# growleds.net
KiCad netlist of a schematic drawn in EAGLE
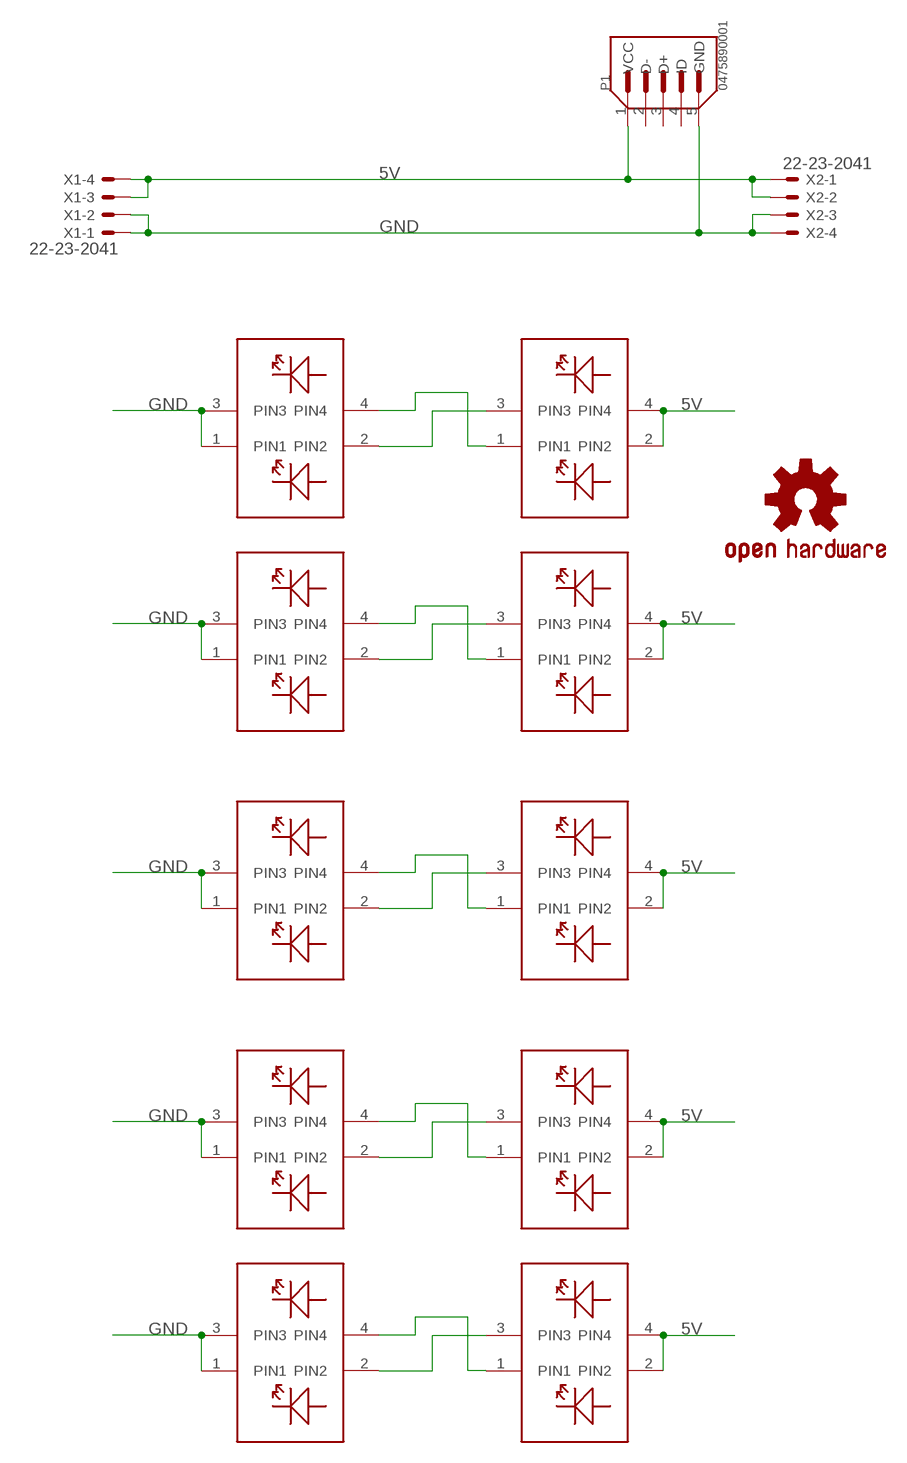
[diagram p0: schematic, sheet 1]

(export (version "E")
  (design (tool "Eeschema 10.0.6"))
  (components
    (comp (ref "LOGO1")
      (value "OSHW-LOGOM-COPPER")
      (footprint "eagle-import:OSHW-LOGO-M_COPPER")
      (libsource (lib "eagle-import") (part "OSHW-LOGOM-COPPER"))
    )
    (comp (ref "P1")
      (value "0475890001")
      (footprint "eagle-import:MOLEX_0475890001")
      (fields (field (name "MF") "Molex"))
      (libsource (lib "eagle-import") (part "0475890001"))
    )
    (comp (ref "U$1")
      (value "RBLED")
      (footprint "eagle-import:4-PLCC")
      (libsource (lib "eagle-import") (part "RBLED"))
    )
    (comp (ref "U$2")
      (value "RBLED")
      (footprint "eagle-import:4-PLCC")
      (libsource (lib "eagle-import") (part "RBLED"))
    )
    (comp (ref "U$3")
      (value "RBLED")
      (footprint "eagle-import:4-PLCC")
      (libsource (lib "eagle-import") (part "RBLED"))
    )
    (comp (ref "U$4")
      (value "RBLED")
      (footprint "eagle-import:4-PLCC")
      (libsource (lib "eagle-import") (part "RBLED"))
    )
    (comp (ref "U$5")
      (value "RBLED")
      (footprint "eagle-import:4-PLCC")
      (libsource (lib "eagle-import") (part "RBLED"))
    )
    (comp (ref "U$6")
      (value "RBLED")
      (footprint "eagle-import:4-PLCC")
      (libsource (lib "eagle-import") (part "RBLED"))
    )
    (comp (ref "U$7")
      (value "RBLED")
      (footprint "eagle-import:4-PLCC")
      (libsource (lib "eagle-import") (part "RBLED"))
    )
    (comp (ref "U$8")
      (value "RBLED")
      (footprint "eagle-import:4-PLCC")
      (libsource (lib "eagle-import") (part "RBLED"))
    )
    (comp (ref "U$9")
      (value "RBLED")
      (footprint "eagle-import:4-PLCC")
      (libsource (lib "eagle-import") (part "RBLED"))
    )
    (comp (ref "U$10")
      (value "RBLED")
      (footprint "eagle-import:4-PLCC")
      (libsource (lib "eagle-import") (part "RBLED"))
    )
    (comp (ref "X1")
      (value "22-23-2041")
      (footprint "eagle-import:22-23-2041")
      (fields (field (name "MF") "MOLEX"))
      (libsource (lib "eagle-import") (part "22-23-2041"))
    )
    (comp (ref "X2")
      (value "22-23-2041")
      (footprint "eagle-import:22-23-2041")
      (fields (field (name "MF") "MOLEX"))
      (libsource (lib "eagle-import") (part "22-23-2041"))
    )
  )
  (nets
    (net (code "1") (name "/5V") (class "Default")
      (node (ref "P1") (pin "1") (pinfunction "VCC_1") (pintype "power_in"))
      (node (ref "U$10") (pin "2") (pinfunction "PIN2_2") (pintype "bidirectional"))
      (node (ref "U$10") (pin "4") (pinfunction "PIN4_4") (pintype "bidirectional"))
      (node (ref "U$2") (pin "2") (pinfunction "PIN2_2") (pintype "bidirectional"))
      (node (ref "U$2") (pin "4") (pinfunction "PIN4_4") (pintype "bidirectional"))
      (node (ref "U$4") (pin "2") (pinfunction "PIN2_2") (pintype "bidirectional"))
      (node (ref "U$4") (pin "4") (pinfunction "PIN4_4") (pintype "bidirectional"))
      (node (ref "U$6") (pin "2") (pinfunction "PIN2_2") (pintype "bidirectional"))
      (node (ref "U$6") (pin "4") (pinfunction "PIN4_4") (pintype "bidirectional"))
      (node (ref "U$8") (pin "2") (pinfunction "PIN2_2") (pintype "bidirectional"))
      (node (ref "U$8") (pin "4") (pinfunction "PIN4_4") (pintype "bidirectional"))
      (node (ref "X1") (pin "3") (pinfunction "S_3") (pintype "passive"))
      (node (ref "X1") (pin "4") (pinfunction "S_4") (pintype "passive"))
      (node (ref "X2") (pin "1") (pinfunction "S_1") (pintype "passive"))
      (node (ref "X2") (pin "2") (pinfunction "S_2") (pintype "passive"))
    )
    (net (code "2") (name "/GND") (class "Default")
      (node (ref "P1") (pin "5") (pinfunction "GND_5") (pintype "power_in"))
      (node (ref "U$1") (pin "1") (pinfunction "PIN1_1") (pintype "bidirectional"))
      (node (ref "U$1") (pin "3") (pinfunction "PIN3_3") (pintype "bidirectional"))
      (node (ref "U$3") (pin "1") (pinfunction "PIN1_1") (pintype "bidirectional"))
      (node (ref "U$3") (pin "3") (pinfunction "PIN3_3") (pintype "bidirectional"))
      (node (ref "U$5") (pin "1") (pinfunction "PIN1_1") (pintype "bidirectional"))
      (node (ref "U$5") (pin "3") (pinfunction "PIN3_3") (pintype "bidirectional"))
      (node (ref "U$7") (pin "1") (pinfunction "PIN1_1") (pintype "bidirectional"))
      (node (ref "U$7") (pin "3") (pinfunction "PIN3_3") (pintype "bidirectional"))
      (node (ref "U$9") (pin "1") (pinfunction "PIN1_1") (pintype "bidirectional"))
      (node (ref "U$9") (pin "3") (pinfunction "PIN3_3") (pintype "bidirectional"))
      (node (ref "X1") (pin "1") (pinfunction "S_1") (pintype "passive"))
      (node (ref "X1") (pin "2") (pinfunction "S_2") (pintype "passive"))
      (node (ref "X2") (pin "3") (pinfunction "S_3") (pintype "passive"))
      (node (ref "X2") (pin "4") (pinfunction "S_4") (pintype "passive"))
    )
    (net (code "3") (name "Net-(U$1-PIN2)") (class "Default")
      (node (ref "U$1") (pin "2") (pinfunction "PIN2_2") (pintype "bidirectional"))
      (node (ref "U$2") (pin "3") (pinfunction "PIN3_3") (pintype "bidirectional"))
    )
    (net (code "4") (name "Net-(U$1-PIN4)") (class "Default")
      (node (ref "U$1") (pin "4") (pinfunction "PIN4_4") (pintype "bidirectional"))
      (node (ref "U$2") (pin "1") (pinfunction "PIN1_1") (pintype "bidirectional"))
    )
    (net (code "5") (name "Net-(U$3-PIN2)") (class "Default")
      (node (ref "U$3") (pin "2") (pinfunction "PIN2_2") (pintype "bidirectional"))
      (node (ref "U$4") (pin "3") (pinfunction "PIN3_3") (pintype "bidirectional"))
    )
    (net (code "6") (name "Net-(U$3-PIN4)") (class "Default")
      (node (ref "U$3") (pin "4") (pinfunction "PIN4_4") (pintype "bidirectional"))
      (node (ref "U$4") (pin "1") (pinfunction "PIN1_1") (pintype "bidirectional"))
    )
    (net (code "7") (name "Net-(U$5-PIN2)") (class "Default")
      (node (ref "U$5") (pin "2") (pinfunction "PIN2_2") (pintype "bidirectional"))
      (node (ref "U$6") (pin "3") (pinfunction "PIN3_3") (pintype "bidirectional"))
    )
    (net (code "8") (name "Net-(U$5-PIN4)") (class "Default")
      (node (ref "U$5") (pin "4") (pinfunction "PIN4_4") (pintype "bidirectional"))
      (node (ref "U$6") (pin "1") (pinfunction "PIN1_1") (pintype "bidirectional"))
    )
    (net (code "9") (name "Net-(U$7-PIN2)") (class "Default")
      (node (ref "U$7") (pin "2") (pinfunction "PIN2_2") (pintype "bidirectional"))
      (node (ref "U$8") (pin "3") (pinfunction "PIN3_3") (pintype "bidirectional"))
    )
    (net (code "10") (name "Net-(U$7-PIN4)") (class "Default")
      (node (ref "U$7") (pin "4") (pinfunction "PIN4_4") (pintype "bidirectional"))
      (node (ref "U$8") (pin "1") (pinfunction "PIN1_1") (pintype "bidirectional"))
    )
    (net (code "11") (name "Net-(U$10-PIN1)") (class "Default")
      (node (ref "U$10") (pin "1") (pinfunction "PIN1_1") (pintype "bidirectional"))
      (node (ref "U$9") (pin "4") (pinfunction "PIN4_4") (pintype "bidirectional"))
    )
    (net (code "12") (name "Net-(U$10-PIN3)") (class "Default")
      (node (ref "U$10") (pin "3") (pinfunction "PIN3_3") (pintype "bidirectional"))
      (node (ref "U$9") (pin "2") (pinfunction "PIN2_2") (pintype "bidirectional"))
    )
    (net (code "13") (name "unconnected-(P1-D+-Pad3)") (class "Default")
      (node (ref "P1") (pin "3") (pinfunction "D+_3") (pintype "bidirectional"))
    )
    (net (code "14") (name "unconnected-(P1-D--Pad2)") (class "Default")
      (node (ref "P1") (pin "2") (pinfunction "D-_2") (pintype "bidirectional"))
    )
    (net (code "15") (name "unconnected-(P1-ID-Pad4)") (class "Default")
      (node (ref "P1") (pin "4") (pinfunction "ID_4") (pintype "bidirectional"))
    )
  )
)
